# zigbee.net
KiCad netlist of a schematic drawn in EAGLE
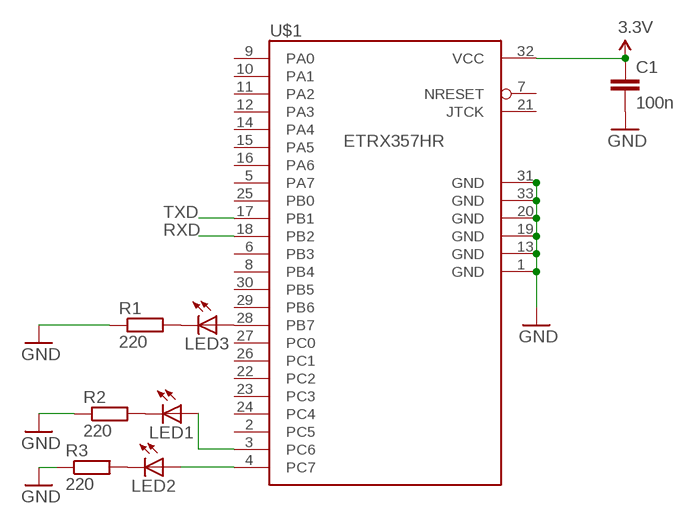
[diagram p0: schematic, sheet 1]

(export (version "E")
  (design (tool "Eeschema 10.0.6"))
  (components
    (comp (ref "C1")
      (value "100n")
      (footprint "eagle-import:C0805")
      (libsource (lib "eagle-import") (part "C-EUC0805"))
    )
    (comp (ref "LED1")
      (value "LED1206")
      (footprint "eagle-import:LED-1206")
      (libsource (lib "eagle-import") (part "LED1206"))
    )
    (comp (ref "LED2")
      (value "LED1206")
      (footprint "eagle-import:LED-1206")
      (libsource (lib "eagle-import") (part "LED1206"))
    )
    (comp (ref "LED3")
      (value "LED1206")
      (footprint "eagle-import:LED-1206")
      (libsource (lib "eagle-import") (part "LED1206"))
    )
    (comp (ref "R1")
      (value "220")
      (footprint "eagle-import:M0805")
      (libsource (lib "eagle-import") (part "R-EU_M0805"))
    )
    (comp (ref "R2")
      (value "220")
      (footprint "eagle-import:M0805")
      (libsource (lib "eagle-import") (part "R-EU_M0805"))
    )
    (comp (ref "R3")
      (value "220")
      (footprint "eagle-import:M0805")
      (libsource (lib "eagle-import") (part "R-EU_M0805"))
    )
    (comp (ref "U$1")
      (value "ETRX357HR")
      (footprint "eagle-import:ETRX3")
      (libsource (lib "eagle-import") (part "ETRX357HR"))
    )
  )
  (nets
    (net (code "1") (name "/RXD") (class "Default")
      (node (ref "U$1") (pin "18") (pinfunction "PB2_18") (pintype "bidirectional"))
    )
    (net (code "2") (name "/TXD") (class "Default")
      (node (ref "U$1") (pin "17") (pinfunction "PB1_17") (pintype "bidirectional"))
    )
    (net (code "3") (name "3.3V") (class "Default")
      (node (ref "C1") (pin "1") (pinfunction "1_1") (pintype "passive"))
      (node (ref "U$1") (pin "32") (pinfunction "VCC_32") (pintype "power_in"))
    )
    (net (code "4") (name "GND") (class "Default")
      (node (ref "C1") (pin "2") (pinfunction "2_2") (pintype "passive"))
      (node (ref "R1") (pin "1") (pinfunction "1_1") (pintype "passive"))
      (node (ref "R2") (pin "1") (pinfunction "1_1") (pintype "passive"))
      (node (ref "R3") (pin "1") (pinfunction "1_1") (pintype "passive"))
      (node (ref "U$1") (pin "1") (pinfunction "GND_1") (pintype "power_in"))
      (node (ref "U$1") (pin "13") (pinfunction "GND_13") (pintype "power_in"))
      (node (ref "U$1") (pin "19") (pinfunction "GND_19") (pintype "power_in"))
      (node (ref "U$1") (pin "20") (pinfunction "GND_20") (pintype "power_in"))
      (node (ref "U$1") (pin "31") (pinfunction "GND_31") (pintype "power_in"))
      (node (ref "U$1") (pin "33") (pinfunction "GND_33") (pintype "power_in"))
    )
    (net (code "5") (name "Net-(LED1-PadC)") (class "Default")
      (node (ref "LED1") (pin "C") (pinfunction "C_C") (pintype "passive"))
      (node (ref "R2") (pin "2") (pinfunction "2_2") (pintype "passive"))
    )
    (net (code "6") (name "Net-(LED2-PadC)") (class "Default")
      (node (ref "LED2") (pin "C") (pinfunction "C_C") (pintype "passive"))
      (node (ref "R3") (pin "2") (pinfunction "2_2") (pintype "passive"))
    )
    (net (code "7") (name "Net-(LED3-PadC)") (class "Default")
      (node (ref "LED3") (pin "C") (pinfunction "C_C") (pintype "passive"))
      (node (ref "R1") (pin "2") (pinfunction "2_2") (pintype "passive"))
    )
    (net (code "8") (name "Net-(U$1-PB7)") (class "Default")
      (node (ref "LED3") (pin "A") (pinfunction "A_A") (pintype "passive"))
      (node (ref "U$1") (pin "28") (pinfunction "PB7_28") (pintype "bidirectional"))
    )
    (net (code "9") (name "Net-(U$1-PC6)") (class "Default")
      (node (ref "LED1") (pin "A") (pinfunction "A_A") (pintype "passive"))
      (node (ref "U$1") (pin "3") (pinfunction "PC6_3") (pintype "bidirectional"))
    )
    (net (code "10") (name "Net-(U$1-PC7)") (class "Default")
      (node (ref "LED2") (pin "A") (pinfunction "A_A") (pintype "passive"))
      (node (ref "U$1") (pin "4") (pinfunction "PC7_4") (pintype "bidirectional"))
    )
    (net (code "11") (name "unconnected-(U$1-JTCK-Pad21)") (class "Default")
      (node (ref "U$1") (pin "21") (pinfunction "JTCK_21") (pintype "bidirectional"))
    )
    (net (code "12") (name "unconnected-(U$1-NRESET-Pad7)") (class "Default")
      (node (ref "U$1") (pin "7") (pinfunction "NRESET_7") (pintype "bidirectional"))
    )
    (net (code "13") (name "unconnected-(U$1-PA0-Pad9)") (class "Default")
      (node (ref "U$1") (pin "9") (pinfunction "PA0_9") (pintype "bidirectional"))
    )
    (net (code "14") (name "unconnected-(U$1-PA1-Pad10)") (class "Default")
      (node (ref "U$1") (pin "10") (pinfunction "PA1_10") (pintype "bidirectional"))
    )
    (net (code "15") (name "unconnected-(U$1-PA2-Pad11)") (class "Default")
      (node (ref "U$1") (pin "11") (pinfunction "PA2_11") (pintype "bidirectional"))
    )
    (net (code "16") (name "unconnected-(U$1-PA3-Pad12)") (class "Default")
      (node (ref "U$1") (pin "12") (pinfunction "PA3_12") (pintype "bidirectional"))
    )
    (net (code "17") (name "unconnected-(U$1-PA4-Pad14)") (class "Default")
      (node (ref "U$1") (pin "14") (pinfunction "PA4_14") (pintype "bidirectional"))
    )
    (net (code "18") (name "unconnected-(U$1-PA5-Pad15)") (class "Default")
      (node (ref "U$1") (pin "15") (pinfunction "PA5_15") (pintype "bidirectional"))
    )
    (net (code "19") (name "unconnected-(U$1-PA6-Pad16)") (class "Default")
      (node (ref "U$1") (pin "16") (pinfunction "PA6_16") (pintype "bidirectional"))
    )
    (net (code "20") (name "unconnected-(U$1-PA7-Pad5)") (class "Default")
      (node (ref "U$1") (pin "5") (pinfunction "PA7_5") (pintype "bidirectional"))
    )
    (net (code "21") (name "unconnected-(U$1-PB0-Pad25)") (class "Default")
      (node (ref "U$1") (pin "25") (pinfunction "PB0_25") (pintype "bidirectional"))
    )
    (net (code "22") (name "unconnected-(U$1-PB3-Pad6)") (class "Default")
      (node (ref "U$1") (pin "6") (pinfunction "PB3_6") (pintype "bidirectional"))
    )
    (net (code "23") (name "unconnected-(U$1-PB4-Pad8)") (class "Default")
      (node (ref "U$1") (pin "8") (pinfunction "PB4_8") (pintype "bidirectional"))
    )
    (net (code "24") (name "unconnected-(U$1-PB5-Pad30)") (class "Default")
      (node (ref "U$1") (pin "30") (pinfunction "PB5_30") (pintype "bidirectional"))
    )
    (net (code "25") (name "unconnected-(U$1-PB6-Pad29)") (class "Default")
      (node (ref "U$1") (pin "29") (pinfunction "PB6_29") (pintype "bidirectional"))
    )
    (net (code "26") (name "unconnected-(U$1-PC0-Pad27)") (class "Default")
      (node (ref "U$1") (pin "27") (pinfunction "PC0_27") (pintype "bidirectional"))
    )
    (net (code "27") (name "unconnected-(U$1-PC1-Pad26)") (class "Default")
      (node (ref "U$1") (pin "26") (pinfunction "PC1_26") (pintype "bidirectional"))
    )
    (net (code "28") (name "unconnected-(U$1-PC2-Pad22)") (class "Default")
      (node (ref "U$1") (pin "22") (pinfunction "PC2_22") (pintype "bidirectional"))
    )
    (net (code "29") (name "unconnected-(U$1-PC3-Pad23)") (class "Default")
      (node (ref "U$1") (pin "23") (pinfunction "PC3_23") (pintype "bidirectional"))
    )
    (net (code "30") (name "unconnected-(U$1-PC4-Pad24)") (class "Default")
      (node (ref "U$1") (pin "24") (pinfunction "PC4_24") (pintype "bidirectional"))
    )
    (net (code "31") (name "unconnected-(U$1-PC5-Pad2)") (class "Default")
      (node (ref "U$1") (pin "2") (pinfunction "PC5_2") (pintype "bidirectional"))
    )
  )
)
